# main-stm32-pdipopto-small.net
KiCad netlist of a schematic drawn in EAGLE
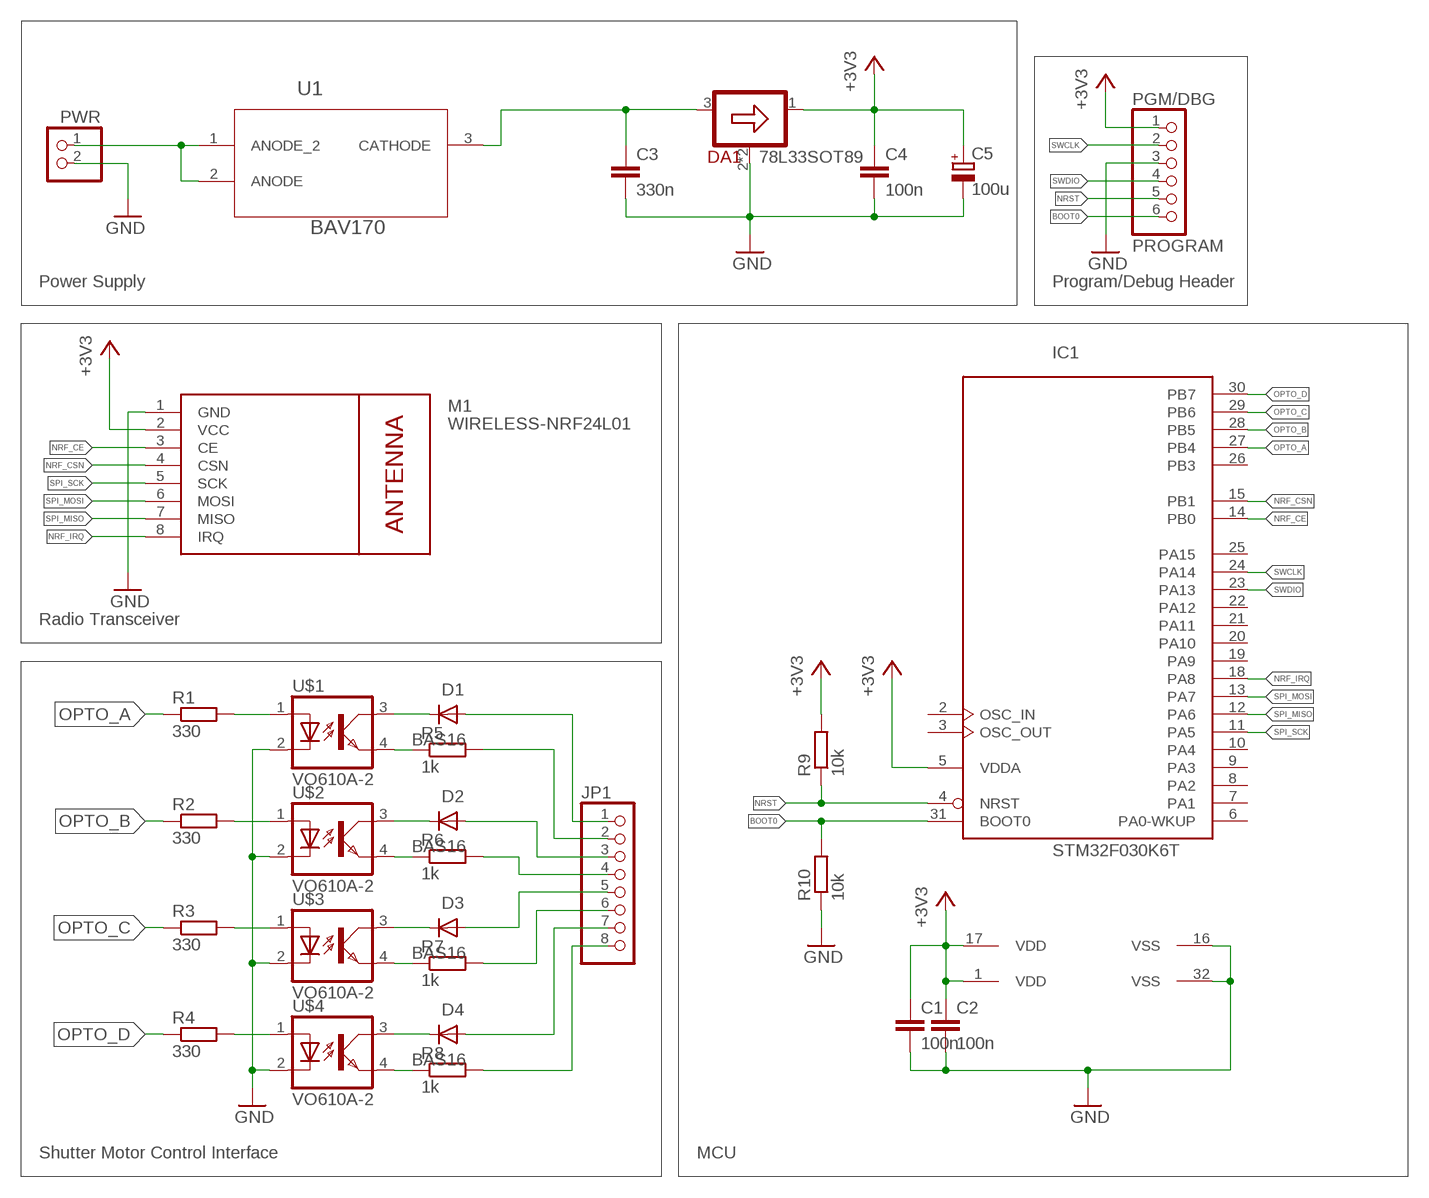
[diagram p0: schematic, sheet 1]

(export (version "E")
  (design (tool "Eeschema 10.0.6"))
  (components
    (comp (ref "C1")
      (value "100n")
      (footprint "eagle-import:C0805")
      (libsource (lib "eagle-import") (part "C-EUC0805"))
    )
    (comp (ref "C2")
      (value "100n")
      (footprint "eagle-import:C0805")
      (libsource (lib "eagle-import") (part "C-EUC0805"))
    )
    (comp (ref "C3")
      (value "330n")
      (footprint "eagle-import:C0805")
      (libsource (lib "eagle-import") (part "C-EUC0805"))
    )
    (comp (ref "C4")
      (value "100n")
      (footprint "eagle-import:C0805")
      (libsource (lib "eagle-import") (part "C-EUC0805"))
    )
    (comp (ref "C5")
      (value "100u")
      (footprint "eagle-import:UD-5X5,8_NICHICON")
      (libsource (lib "eagle-import") (part "CPOL-EUUD-5X5,8"))
    )
    (comp (ref "D1")
      (value "BAS16")
      (footprint "eagle-import:SOT23")
      (libsource (lib "eagle-import") (part "BAS16"))
    )
    (comp (ref "D2")
      (value "BAS16")
      (footprint "eagle-import:SOT23")
      (libsource (lib "eagle-import") (part "BAS16"))
    )
    (comp (ref "D3")
      (value "BAS16")
      (footprint "eagle-import:SOT23")
      (libsource (lib "eagle-import") (part "BAS16"))
    )
    (comp (ref "D4")
      (value "BAS16")
      (footprint "eagle-import:SOT23")
      (libsource (lib "eagle-import") (part "BAS16"))
    )
    (comp (ref "DA1")
      (value "78L33SOT89")
      (footprint "eagle-import:SOT89")
      (libsource (lib "eagle-import") (part "78L33SOT89"))
    )
    (comp (ref "IC1")
      (value "STM32F030K6T")
      (footprint "eagle-import:LQFP32")
      (libsource (lib "eagle-import") (part "STM32F030KT6"))
    )
    (comp (ref "JP1")
      (value "PINHD-1X8")
      (footprint "eagle-import:1X08")
      (libsource (lib "eagle-import") (part "PINHD-1X8"))
    )
    (comp (ref "M1")
      (value "WIRELESS-NRF24L01")
      (footprint "eagle-import:WIRELESS-NRF24L01")
      (libsource (lib "eagle-import") (part "WIRELESS-NRF24L01"))
    )
    (comp (ref "PGM/DBG")
      (value "PROGRAM")
      (footprint "eagle-import:1X06")
      (libsource (lib "eagle-import") (part "PINHD-1X6"))
    )
    (comp (ref "PWR")
      (value "PINHD-1X2")
      (footprint "eagle-import:1X02")
      (libsource (lib "eagle-import") (part "PINHD-1X2"))
    )
    (comp (ref "R1")
      (value "330")
      (footprint "eagle-import:R0805")
      (libsource (lib "eagle-import") (part "R-EU_R0805"))
    )
    (comp (ref "R2")
      (value "330")
      (footprint "eagle-import:R0805")
      (libsource (lib "eagle-import") (part "R-EU_R0805"))
    )
    (comp (ref "R3")
      (value "330")
      (footprint "eagle-import:R0805")
      (libsource (lib "eagle-import") (part "R-EU_R0805"))
    )
    (comp (ref "R4")
      (value "330")
      (footprint "eagle-import:R0805")
      (libsource (lib "eagle-import") (part "R-EU_R0805"))
    )
    (comp (ref "R5")
      (value "1k")
      (footprint "eagle-import:R0805")
      (libsource (lib "eagle-import") (part "R-EU_R0805"))
    )
    (comp (ref "R6")
      (value "1k")
      (footprint "eagle-import:R0805")
      (libsource (lib "eagle-import") (part "R-EU_R0805"))
    )
    (comp (ref "R7")
      (value "1k")
      (footprint "eagle-import:R0805")
      (libsource (lib "eagle-import") (part "R-EU_R0805"))
    )
    (comp (ref "R8")
      (value "1k")
      (footprint "eagle-import:R0805")
      (libsource (lib "eagle-import") (part "R-EU_R0805"))
    )
    (comp (ref "R9")
      (value "10k")
      (footprint "eagle-import:R0805")
      (libsource (lib "eagle-import") (part "R-EU_R0805"))
    )
    (comp (ref "R10")
      (value "10k")
      (footprint "eagle-import:R0805")
      (libsource (lib "eagle-import") (part "R-EU_R0805"))
    )
    (comp (ref "U$1")
      (value "VO610A-2")
      (footprint "eagle-import:DIL04")
      (libsource (lib "eagle-import") (part "VO610A-2"))
    )
    (comp (ref "U$2")
      (value "VO610A-2")
      (footprint "eagle-import:DIL04")
      (libsource (lib "eagle-import") (part "VO610A-2"))
    )
    (comp (ref "U$3")
      (value "VO610A-2")
      (footprint "eagle-import:DIL04")
      (libsource (lib "eagle-import") (part "VO610A-2"))
    )
    (comp (ref "U$4")
      (value "VO610A-2")
      (footprint "eagle-import:DIL04")
      (libsource (lib "eagle-import") (part "VO610A-2"))
    )
    (comp (ref "U1")
      (value "BAV170")
      (footprint "eagle-import:SOT95P240X110-3N")
      (libsource (lib "eagle-import") (part "BAV170"))
    )
  )
  (nets
    (net (code "1") (name "+3V3") (class "Default")
      (node (ref "C1") (pin "1") (pinfunction "1_1") (pintype "passive"))
      (node (ref "C2") (pin "1") (pinfunction "1_1") (pintype "passive"))
      (node (ref "C4") (pin "1") (pinfunction "1_1") (pintype "passive"))
      (node (ref "C5") (pin "+") (pinfunction "+_+") (pintype "passive"))
      (node (ref "DA1") (pin "1") (pinfunction "OUT_1") (pintype "power_in"))
      (node (ref "IC1") (pin "1") (pinfunction "VDD_1") (pintype "power_in"))
      (node (ref "IC1") (pin "17") (pinfunction "VDD_17") (pintype "power_in"))
      (node (ref "IC1") (pin "5") (pinfunction "VDDA_5") (pintype "power_in"))
      (node (ref "M1") (pin "2") (pinfunction "VCC_2") (pintype "power_in"))
      (node (ref "PGM/DBG") (pin "1") (pinfunction "1_1") (pintype "passive"))
      (node (ref "R9") (pin "2") (pinfunction "2_2") (pintype "passive"))
    )
    (net (code "2") (name "BOOT0") (class "Default")
      (node (ref "IC1") (pin "31") (pinfunction "BOOT0_31") (pintype "input"))
      (node (ref "PGM/DBG") (pin "6") (pinfunction "6_6") (pintype "passive"))
      (node (ref "R10") (pin "2") (pinfunction "2_2") (pintype "passive"))
    )
    (net (code "3") (name "GND") (class "Default")
      (node (ref "C1") (pin "2") (pinfunction "2_2") (pintype "passive"))
      (node (ref "C2") (pin "2") (pinfunction "2_2") (pintype "passive"))
      (node (ref "C3") (pin "2") (pinfunction "2_2") (pintype "passive"))
      (node (ref "C4") (pin "2") (pinfunction "2_2") (pintype "passive"))
      (node (ref "C5") (pin "-") (pinfunction "-_-") (pintype "passive"))
      (node (ref "DA1") (pin "2") (pinfunction "GND_2") (pintype "power_in"))
      (node (ref "DA1") (pin "2@1") (pinfunction "GND_2@1") (pintype "power_in"))
      (node (ref "IC1") (pin "16") (pinfunction "VSS_16") (pintype "power_in"))
      (node (ref "IC1") (pin "32") (pinfunction "VSS_32") (pintype "power_in"))
      (node (ref "M1") (pin "1") (pinfunction "GND_1") (pintype "power_in"))
      (node (ref "PGM/DBG") (pin "3") (pinfunction "3_3") (pintype "passive"))
      (node (ref "PWR") (pin "2") (pinfunction "2_2") (pintype "passive"))
      (node (ref "R10") (pin "1") (pinfunction "1_1") (pintype "passive"))
      (node (ref "U$1") (pin "2") (pinfunction "C_2") (pintype "passive"))
      (node (ref "U$2") (pin "2") (pinfunction "C_2") (pintype "passive"))
      (node (ref "U$3") (pin "2") (pinfunction "C_2") (pintype "passive"))
      (node (ref "U$4") (pin "2") (pinfunction "C_2") (pintype "passive"))
    )
    (net (code "4") (name "NRF_CE") (class "Default")
      (node (ref "IC1") (pin "14") (pinfunction "PB0_14") (pintype "bidirectional"))
      (node (ref "M1") (pin "3") (pinfunction "CE_3") (pintype "bidirectional"))
    )
    (net (code "5") (name "NRF_CSN") (class "Default")
      (node (ref "IC1") (pin "15") (pinfunction "PB1_15") (pintype "bidirectional"))
      (node (ref "M1") (pin "4") (pinfunction "CSN_4") (pintype "bidirectional"))
    )
    (net (code "6") (name "NRF_IRQ") (class "Default")
      (node (ref "IC1") (pin "18") (pinfunction "PA8_18") (pintype "bidirectional"))
      (node (ref "M1") (pin "8") (pinfunction "IRQ_8") (pintype "bidirectional"))
    )
    (net (code "7") (name "NRST") (class "Default")
      (node (ref "IC1") (pin "4") (pinfunction "NRST_4") (pintype "bidirectional"))
      (node (ref "PGM/DBG") (pin "5") (pinfunction "5_5") (pintype "passive"))
      (node (ref "R9") (pin "1") (pinfunction "1_1") (pintype "passive"))
    )
    (net (code "8") (name "Net-(D1-A)") (class "Default")
      (node (ref "D1") (pin "1") (pinfunction "A_1") (pintype "passive"))
      (node (ref "JP1") (pin "1") (pinfunction "1_1") (pintype "passive"))
    )
    (net (code "9") (name "Net-(D1-K)") (class "Default")
      (node (ref "D1") (pin "3") (pinfunction "K_3") (pintype "passive"))
      (node (ref "U$1") (pin "3") (pinfunction "COL_3") (pintype "passive"))
    )
    (net (code "10") (name "Net-(D2-A)") (class "Default")
      (node (ref "D2") (pin "1") (pinfunction "A_1") (pintype "passive"))
      (node (ref "JP1") (pin "3") (pinfunction "3_3") (pintype "passive"))
    )
    (net (code "11") (name "Net-(D2-K)") (class "Default")
      (node (ref "D2") (pin "3") (pinfunction "K_3") (pintype "passive"))
      (node (ref "U$2") (pin "3") (pinfunction "COL_3") (pintype "passive"))
    )
    (net (code "12") (name "Net-(D3-A)") (class "Default")
      (node (ref "D3") (pin "1") (pinfunction "A_1") (pintype "passive"))
      (node (ref "JP1") (pin "5") (pinfunction "5_5") (pintype "passive"))
    )
    (net (code "13") (name "Net-(D3-K)") (class "Default")
      (node (ref "D3") (pin "3") (pinfunction "K_3") (pintype "passive"))
      (node (ref "U$3") (pin "3") (pinfunction "COL_3") (pintype "passive"))
    )
    (net (code "14") (name "Net-(D4-A)") (class "Default")
      (node (ref "D4") (pin "1") (pinfunction "A_1") (pintype "passive"))
      (node (ref "JP1") (pin "7") (pinfunction "7_7") (pintype "passive"))
    )
    (net (code "15") (name "Net-(D4-K)") (class "Default")
      (node (ref "D4") (pin "3") (pinfunction "K_3") (pintype "passive"))
      (node (ref "U$4") (pin "3") (pinfunction "COL_3") (pintype "passive"))
    )
    (net (code "16") (name "Net-(DA1-IN)") (class "Default")
      (node (ref "C3") (pin "1") (pinfunction "1_1") (pintype "passive"))
      (node (ref "DA1") (pin "3") (pinfunction "IN_3") (pintype "power_in"))
      (node (ref "U1") (pin "3") (pinfunction "CATHODE_3") (pintype "passive"))
    )
    (net (code "17") (name "Net-(JP1-Pad2)") (class "Default")
      (node (ref "JP1") (pin "2") (pinfunction "2_2") (pintype "passive"))
      (node (ref "R5") (pin "2") (pinfunction "2_2") (pintype "passive"))
    )
    (net (code "18") (name "Net-(JP1-Pad4)") (class "Default")
      (node (ref "JP1") (pin "4") (pinfunction "4_4") (pintype "passive"))
      (node (ref "R6") (pin "2") (pinfunction "2_2") (pintype "passive"))
    )
    (net (code "19") (name "Net-(JP1-Pad6)") (class "Default")
      (node (ref "JP1") (pin "6") (pinfunction "6_6") (pintype "passive"))
      (node (ref "R7") (pin "2") (pinfunction "2_2") (pintype "passive"))
    )
    (net (code "20") (name "Net-(JP1-Pad8)") (class "Default")
      (node (ref "JP1") (pin "8") (pinfunction "8_8") (pintype "passive"))
      (node (ref "R8") (pin "2") (pinfunction "2_2") (pintype "passive"))
    )
    (net (code "21") (name "Net-(U$1-A)") (class "Default")
      (node (ref "R1") (pin "2") (pinfunction "2_2") (pintype "passive"))
      (node (ref "U$1") (pin "1") (pinfunction "A_1") (pintype "passive"))
    )
    (net (code "22") (name "Net-(U$1-EMIT)") (class "Default")
      (node (ref "R5") (pin "1") (pinfunction "1_1") (pintype "passive"))
      (node (ref "U$1") (pin "4") (pinfunction "EMIT_4") (pintype "passive"))
    )
    (net (code "23") (name "Net-(U$2-A)") (class "Default")
      (node (ref "R2") (pin "2") (pinfunction "2_2") (pintype "passive"))
      (node (ref "U$2") (pin "1") (pinfunction "A_1") (pintype "passive"))
    )
    (net (code "24") (name "Net-(U$2-EMIT)") (class "Default")
      (node (ref "R6") (pin "1") (pinfunction "1_1") (pintype "passive"))
      (node (ref "U$2") (pin "4") (pinfunction "EMIT_4") (pintype "passive"))
    )
    (net (code "25") (name "Net-(U$3-A)") (class "Default")
      (node (ref "R3") (pin "2") (pinfunction "2_2") (pintype "passive"))
      (node (ref "U$3") (pin "1") (pinfunction "A_1") (pintype "passive"))
    )
    (net (code "26") (name "Net-(U$3-EMIT)") (class "Default")
      (node (ref "R7") (pin "1") (pinfunction "1_1") (pintype "passive"))
      (node (ref "U$3") (pin "4") (pinfunction "EMIT_4") (pintype "passive"))
    )
    (net (code "27") (name "Net-(U$4-A)") (class "Default")
      (node (ref "R4") (pin "2") (pinfunction "2_2") (pintype "passive"))
      (node (ref "U$4") (pin "1") (pinfunction "A_1") (pintype "passive"))
    )
    (net (code "28") (name "Net-(U$4-EMIT)") (class "Default")
      (node (ref "R8") (pin "1") (pinfunction "1_1") (pintype "passive"))
      (node (ref "U$4") (pin "4") (pinfunction "EMIT_4") (pintype "passive"))
    )
    (net (code "29") (name "Net-(U1-ANODE)") (class "Default")
      (node (ref "PWR") (pin "1") (pinfunction "1_1") (pintype "passive"))
      (node (ref "U1") (pin "1") (pinfunction "ANODE_2_1") (pintype "passive"))
      (node (ref "U1") (pin "2") (pinfunction "ANODE_2") (pintype "passive"))
    )
    (net (code "30") (name "OPTO_A") (class "Default")
      (node (ref "IC1") (pin "27") (pinfunction "PB4_27") (pintype "bidirectional"))
      (node (ref "R1") (pin "1") (pinfunction "1_1") (pintype "passive"))
    )
    (net (code "31") (name "OPTO_B") (class "Default")
      (node (ref "IC1") (pin "28") (pinfunction "PB5_28") (pintype "bidirectional"))
      (node (ref "R2") (pin "1") (pinfunction "1_1") (pintype "passive"))
    )
    (net (code "32") (name "OPTO_C") (class "Default")
      (node (ref "IC1") (pin "29") (pinfunction "PB6_29") (pintype "bidirectional"))
      (node (ref "R3") (pin "1") (pinfunction "1_1") (pintype "passive"))
    )
    (net (code "33") (name "OPTO_D") (class "Default")
      (node (ref "IC1") (pin "30") (pinfunction "PB7_30") (pintype "bidirectional"))
      (node (ref "R4") (pin "1") (pinfunction "1_1") (pintype "passive"))
    )
    (net (code "34") (name "SPI_MISO") (class "Default")
      (node (ref "IC1") (pin "12") (pinfunction "PA6_12") (pintype "bidirectional"))
      (node (ref "M1") (pin "7") (pinfunction "MISO_7") (pintype "bidirectional"))
    )
    (net (code "35") (name "SPI_MOSI") (class "Default")
      (node (ref "IC1") (pin "13") (pinfunction "PA7_13") (pintype "bidirectional"))
      (node (ref "M1") (pin "6") (pinfunction "MOSI_6") (pintype "bidirectional"))
    )
    (net (code "36") (name "SPI_SCK") (class "Default")
      (node (ref "IC1") (pin "11") (pinfunction "PA5_11") (pintype "bidirectional"))
      (node (ref "M1") (pin "5") (pinfunction "SCK_5") (pintype "bidirectional"))
    )
    (net (code "37") (name "SWCLK") (class "Default")
      (node (ref "IC1") (pin "24") (pinfunction "PA14_24") (pintype "bidirectional"))
      (node (ref "PGM/DBG") (pin "2") (pinfunction "2_2") (pintype "passive"))
    )
    (net (code "38") (name "SWDIO") (class "Default")
      (node (ref "IC1") (pin "23") (pinfunction "PA13_23") (pintype "bidirectional"))
      (node (ref "PGM/DBG") (pin "4") (pinfunction "4_4") (pintype "passive"))
    )
    (net (code "39") (name "unconnected-(IC1A-OSC_IN-Pad2)") (class "Default")
      (node (ref "IC1") (pin "2") (pinfunction "OSC_IN_2") (pintype "bidirectional"))
    )
    (net (code "40") (name "unconnected-(IC1A-OSC_OUT-Pad3)") (class "Default")
      (node (ref "IC1") (pin "3") (pinfunction "OSC_OUT_3") (pintype "bidirectional"))
    )
    (net (code "41") (name "unconnected-(IC1A-PA0-WKUP-Pad6)") (class "Default")
      (node (ref "IC1") (pin "6") (pinfunction "PA0-WKUP_6") (pintype "bidirectional"))
    )
    (net (code "42") (name "unconnected-(IC1A-PA1-Pad7)") (class "Default")
      (node (ref "IC1") (pin "7") (pinfunction "PA1_7") (pintype "bidirectional"))
    )
    (net (code "43") (name "unconnected-(IC1A-PA2-Pad8)") (class "Default")
      (node (ref "IC1") (pin "8") (pinfunction "PA2_8") (pintype "bidirectional"))
    )
    (net (code "44") (name "unconnected-(IC1A-PA3-Pad9)") (class "Default")
      (node (ref "IC1") (pin "9") (pinfunction "PA3_9") (pintype "bidirectional"))
    )
    (net (code "45") (name "unconnected-(IC1A-PA4-Pad10)") (class "Default")
      (node (ref "IC1") (pin "10") (pinfunction "PA4_10") (pintype "bidirectional"))
    )
    (net (code "46") (name "unconnected-(IC1A-PA9-Pad19)") (class "Default")
      (node (ref "IC1") (pin "19") (pinfunction "PA9_19") (pintype "bidirectional"))
    )
    (net (code "47") (name "unconnected-(IC1A-PA10-Pad20)") (class "Default")
      (node (ref "IC1") (pin "20") (pinfunction "PA10_20") (pintype "bidirectional"))
    )
    (net (code "48") (name "unconnected-(IC1A-PA11-Pad21)") (class "Default")
      (node (ref "IC1") (pin "21") (pinfunction "PA11_21") (pintype "bidirectional"))
    )
    (net (code "49") (name "unconnected-(IC1A-PA12-Pad22)") (class "Default")
      (node (ref "IC1") (pin "22") (pinfunction "PA12_22") (pintype "bidirectional"))
    )
    (net (code "50") (name "unconnected-(IC1A-PA15-Pad25)") (class "Default")
      (node (ref "IC1") (pin "25") (pinfunction "PA15_25") (pintype "bidirectional"))
    )
    (net (code "51") (name "unconnected-(IC1A-PB3-Pad26)") (class "Default")
      (node (ref "IC1") (pin "26") (pinfunction "PB3_26") (pintype "bidirectional"))
    )
  )
)
